# INA219_CH3.net
KiCad netlist of a schematic drawn in Altium Designer
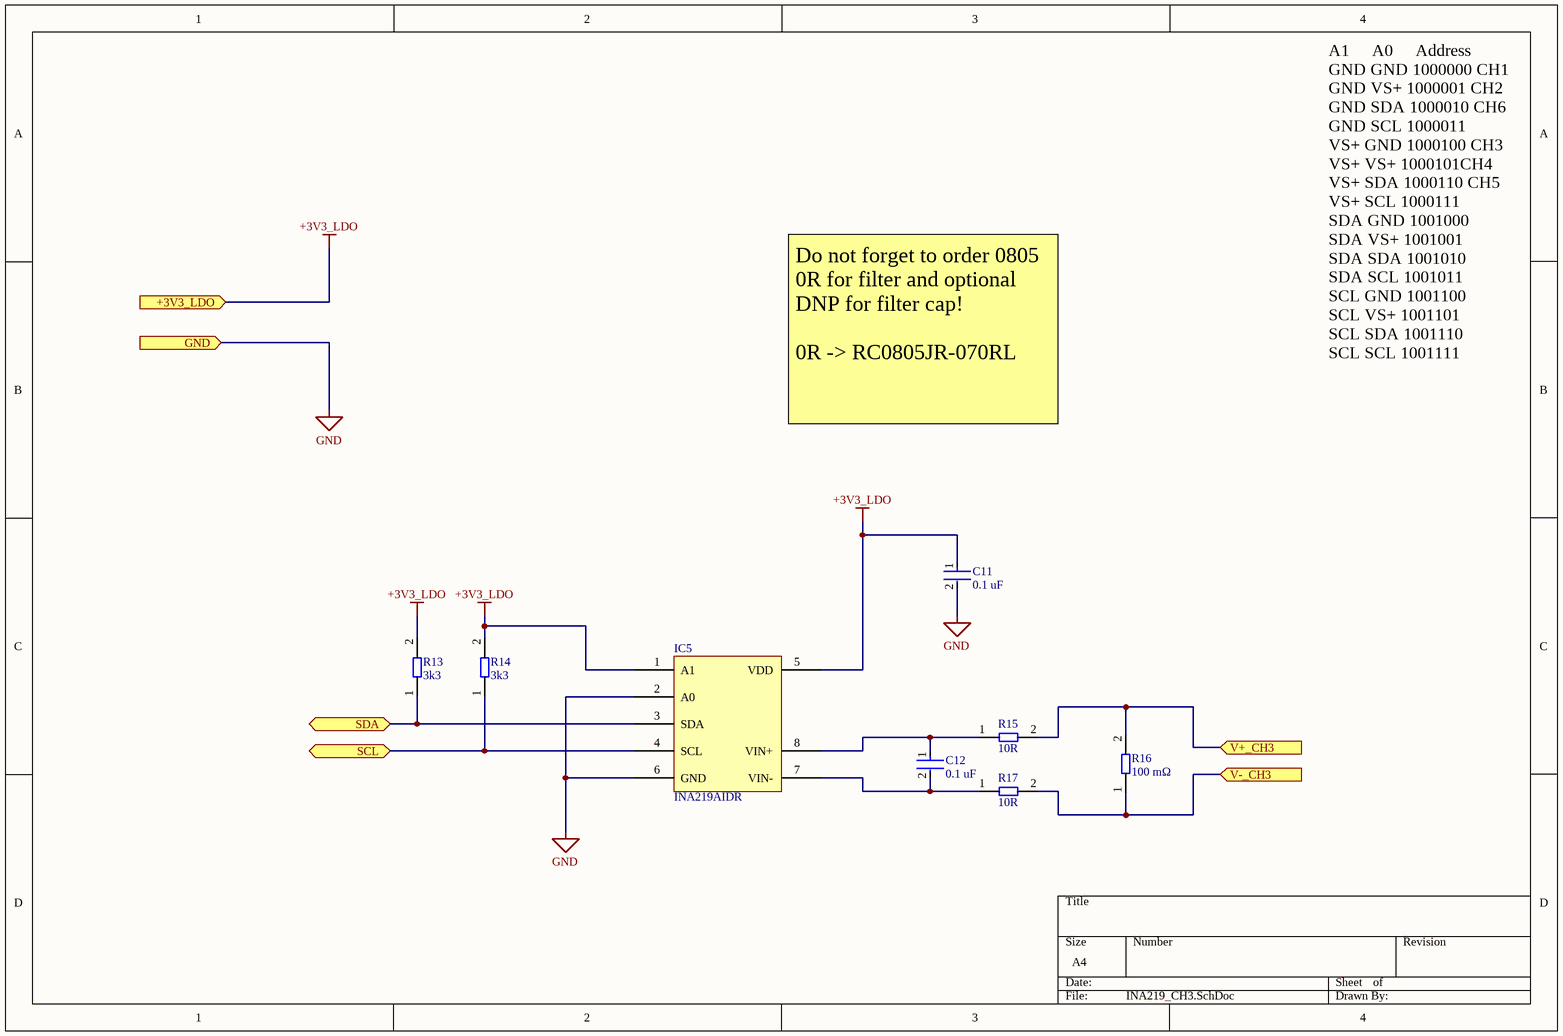
[diagram p0: INA219_CH3.SchDoc]

(export (version "E")
  (design (tool "Eeschema 10.0.6"))
  (components
    (comp (ref "C11")
      (value "0.1 uF")
      (footprint "FP-C0805C-DN-MFG")
      (description "C0805 0.10 μF X7R 30ppm/°C 20.00% 50 V C0805C104M5RAC")
      (fields
        (field (name "MANUFACTURER PART NUMBER") "C0805C104M5RAC")
        (field (name "MANUFACTURER") "KEMET")
      )
      (libsource (lib "Altium Content Vault") (part "b4654b650e69147ec39a6b967a45e02"))
    )
    (comp (ref "C12")
      (value "0.1 uF")
      (footprint "FP-C0805C-DN-MFG")
      (description "C0805 0.10 μF X7R 30ppm/°C 20.00% 50 V C0805C104M5RAC")
      (fields
        (field (name "MANUFACTURER PART NUMBER") "C0805C104M5RAC")
        (field (name "MANUFACTURER") "KEMET")
      )
      (libsource (lib "Altium Content Vault") (part "b4654b650e69147ec39a6b967a45e02"))
    )
    (comp (ref "IC5")
      (value "INA219AIDR")
      (footprint "INA219AIDR")
      (description "Current & Power Monitors & Regulators Zero-Drift,Bi-Dir Crnt/Pwr Monitor")
      (libsource (lib "Callisto Control Board") (part "INA219AIDR"))
    )
    (comp (ref "R13")
      (value "3k3")
      (footprint "0805 Resistor - IPC A")
      (description "Thick Film Resistors - SMD 3.3 kOhms 125 mW 0805 1%\r\nRE0805FRE073K3L")
      (libsource (lib "Callisto Control Board") (part "RE0805FRE073K3L"))
    )
    (comp (ref "R14")
      (value "3k3")
      (footprint "0805 Resistor - IPC A")
      (description "Thick Film Resistors - SMD 3.3 kOhms 125 mW 0805 1%\r\nRE0805FRE073K3L")
      (libsource (lib "Callisto Control Board") (part "RE0805FRE073K3L"))
    )
    (comp (ref "R15")
      (value "10R")
      (footprint "0805 Resistor - IPC A")
      (description "Thick Film Resistors - SMD 10 Ohms 125 mW 0805 1%\r\nRC0805FR-0710RL")
      (libsource (lib "Callisto Control Board") (part "RC0805FR-0710RL"))
    )
    (comp (ref "R16")
      (value "100 mΩ")
      (footprint "PE2512FKM070R1L")
      (description "Current Sense Resistors - SMD 100 mOhms 1 Watt 1 % 75 ppm/C AEC-Q200\r\nPE2512FKM070R1L")
      (libsource (lib "Callisto Control Board") (part "PE2512FKM070R1L"))
    )
    (comp (ref "R17")
      (value "10R")
      (footprint "0805 Resistor - IPC A")
      (description "Thick Film Resistors - SMD 10 Ohms 125 mW 0805 1%\r\nRC0805FR-0710RL")
      (libsource (lib "Callisto Control Board") (part "RC0805FR-0710RL"))
    )
  )
  (nets
    (net (code "1") (name "+3V3_LDO") (class "Default")
      (node (ref "C11") (pin "1") (pinfunction "1_1") (pintype "passive"))
      (node (ref "IC5") (pin "1") (pinfunction "A1_1") (pintype "passive"))
      (node (ref "IC5") (pin "5") (pinfunction "VDD_5") (pintype "passive"))
      (node (ref "R13") (pin "2") (pintype "passive"))
      (node (ref "R14") (pin "2") (pintype "passive"))
    )
    (net (code "2") (name "/SCL") (class "Default")
      (node (ref "IC5") (pin "4") (pinfunction "SCL_4") (pintype "passive"))
      (node (ref "R14") (pin "1") (pintype "passive"))
    )
    (net (code "3") (name "/SDA") (class "Default")
      (node (ref "IC5") (pin "3") (pinfunction "SDA_3") (pintype "passive"))
      (node (ref "R13") (pin "1") (pintype "passive"))
    )
    (net (code "4") (name "/V+_CH3") (class "Default")
      (node (ref "R15") (pin "2") (pintype "passive"))
      (node (ref "R16") (pin "2") (pintype "passive"))
    )
    (net (code "5") (name "/V-_CH3") (class "Default")
      (node (ref "R16") (pin "1") (pintype "passive"))
      (node (ref "R17") (pin "2") (pintype "passive"))
    )
    (net (code "6") (name "GND") (class "Default")
      (node (ref "C11") (pin "2") (pinfunction "2_2") (pintype "passive"))
      (node (ref "IC5") (pin "2") (pinfunction "A0_2") (pintype "passive"))
      (node (ref "IC5") (pin "6") (pinfunction "GND_6") (pintype "passive"))
    )
    (net (code "7") (name "Net-(IC5-VIN+)") (class "Default")
      (node (ref "C12") (pin "1") (pinfunction "1_1") (pintype "passive"))
      (node (ref "IC5") (pin "8") (pinfunction "VIN+_8") (pintype "passive"))
      (node (ref "R15") (pin "1") (pintype "passive"))
    )
    (net (code "8") (name "Net-(IC5-VIN-)") (class "Default")
      (node (ref "C12") (pin "2") (pinfunction "2_2") (pintype "passive"))
      (node (ref "IC5") (pin "7") (pinfunction "VIN-_7") (pintype "passive"))
      (node (ref "R17") (pin "1") (pintype "passive"))
    )
  )
)
